# Power.net
KiCad netlist of a schematic drawn in Altium Designer
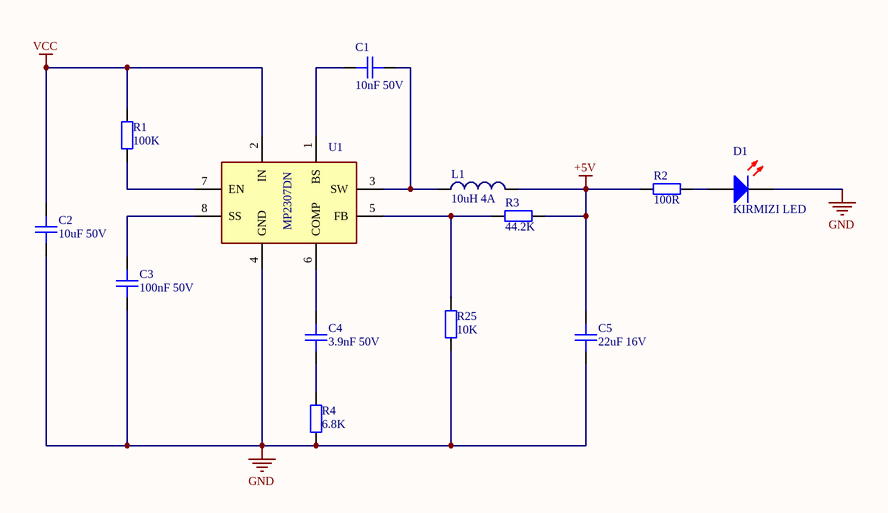
[diagram p0: Power.SchDoc]

(export (version "E")
  (design (tool "Eeschema 10.0.6"))
  (components
    (comp (ref "C1")
      (value "CAP CER 10000PF 50V X7R 0805")
      (footprint "CAP 0805/2012")
      (description "10000pF ±10% 50V Ceramic Capacitor X7R 0805 (2012 Metric)")
      (fields (field (name "DEGER") "10nF 50V"))
      (libsource (lib "PROJE") (part "10nF 50V 0805"))
    )
    (comp (ref "C2")
      (value "CAP CER 10UF 50V X5R 1206")
      (footprint "CAP 1206/3216")
      (description "10µF ±10% 50V Ceramic Capacitor X5R 1206 (3216 Metric)")
      (fields (field (name "DEGER") "10uF 50V"))
      (libsource (lib "PROJE") (part "10uF 50V 1206"))
    )
    (comp (ref "C3")
      (value "CAP CER 0.1UF 50V X7R 0805")
      (footprint "CAP 0805/2012")
      (description "0.1µF ±10% 50V Ceramic Capacitor X7R 0805 (2012 Metric)")
      (fields (field (name "DEGER") "100nF 50V"))
      (libsource (lib "PROJE") (part "100nF 50V 0805"))
    )
    (comp (ref "C4")
      (value "CAP CER 3900PF 50V X7R 0805")
      (footprint "CAP 0805/2012")
      (description "3900pF ±10% 50V Ceramic Capacitor X7R 0805 (2012 Metric)")
      (fields (field (name "DEGER") "3.9nF 50V"))
      (libsource (lib "PROJE") (part "3.9nF 50V 0805"))
    )
    (comp (ref "C5")
      (value "CAP CERAMIC 22UF 16V X7S 20% PAD")
      (footprint "CAP 1206/3216")
      (description "22µF ±20% 16V Ceramic Capacitor X7S 1206 (3216 Metric)")
      (fields (field (name "DEGER") "22uF 16V"))
      (libsource (lib "PROJE") (part "22uF 16V 1206"))
    )
    (comp (ref "D1")
      (value "Red 645nm LED Indication - Discrete 1.8V 0805")
      (footprint "SMD: LED 0805/2012 RED")
      (description "LED RED DIFFUSED 0805 SMD")
      (fields (field (name "DEGER") "KIRMIZI LED"))
      (libsource (lib "PROJE") (part "LED_Kırmızı"))
    )
    (comp (ref "L1")
      (value "FIXED IND 10UH 4A 68 MOHM SMD")
      (footprint "ASPI-0630LR-100M-T15")
      (description "10µH Shielded Molded Inductor 4A 68mOhm Max Nonstandard")
      (fields (field (name "DEGER") "10uH 4A"))
      (libsource (lib "PROJE") (part "10uH 4A"))
    )
    (comp (ref "R1")
      (value "RES SMD 100K OHM 1% 1/8W 0805")
      (footprint "RES_0805")
      (description "100 kOhms ±1% 0.125W, 1/8W Chip Resistor 0805 (2012 Metric) Moisture Resistant Thick Film")
      (fields (field (name "DEGER") "100K"))
      (libsource (lib "PROJE") (part "100K 0805"))
    )
    (comp (ref "R2")
      (value "RES SMD 100 OHM 1% 1/8W 0805")
      (footprint "RES_0805")
      (description "100 Ohms ±1% 0.125W, 1/8W Chip Resistor 0805 (2012 Metric) Moisture Resistant Thick Film")
      (fields (field (name "DEGER") "100R"))
      (libsource (lib "PROJE") (part "100R 0805"))
    )
    (comp (ref "R3")
      (value "RES SMD 44.2K OHM 1% 1/8W 0805")
      (footprint "RES_0805")
      (description "44.2 kOhms ±1% 0.125W, 1/8W Chip Resistor 0805 (2012 Metric) Moisture Resistant Thick Film")
      (fields (field (name "DEGER") "44.2K"))
      (libsource (lib "PROJE") (part "44.2K 0805"))
    )
    (comp (ref "R4")
      (value "RES SMD 6.8K OHM 1% 1/8W 0805")
      (footprint "RES_0805")
      (description "6.8 kOhms ±1% 0.125W, 1/8W Chip Resistor 0805 (2012 Metric) Moisture Resistant Thick Film")
      (fields (field (name "DEGER") "6.8K"))
      (libsource (lib "PROJE") (part "6.8K 0805"))
    )
    (comp (ref "R25")
      (value "RES SMD 10K OHM 1% 1/8W 0805")
      (footprint "RES_0805")
      (description "10 kOhms ±1% 0.125W, 1/8W Chip Resistor 0805 (2012 Metric) Moisture Resistant Thick Film")
      (fields (field (name "DEGER") "10K"))
      (libsource (lib "PROJE") (part "10K 0805"))
    )
    (comp (ref "U1")
      (value "IC REG BUCK ADJUSTABLE 3A 8SOIC")
      (footprint "SOIC8_PAD")
      (fields (field (name "DEGER") "MP2307DN"))
      (libsource (lib "PROJE") (part "MP2307DN"))
    )
  )
  (nets
    (net (code "1") (name "+5V") (class "Default")
      (node (ref "C5") (pin "2") (pinfunction "2_2") (pintype "passive"))
      (node (ref "L1") (pin "2") (pinfunction "2_2") (pintype "passive"))
      (node (ref "R2") (pin "1") (pinfunction "1_1") (pintype "passive"))
      (node (ref "R3") (pin "2") (pinfunction "2_2") (pintype "passive"))
    )
    (net (code "2") (name "GND") (class "Default")
      (node (ref "C2") (pin "1") (pinfunction "1_1") (pintype "passive"))
      (node (ref "C3") (pin "1") (pinfunction "1_1") (pintype "passive"))
      (node (ref "C5") (pin "1") (pinfunction "1_1") (pintype "passive"))
      (node (ref "D1") (pin "2") (pinfunction "K_2") (pintype "passive"))
      (node (ref "R25") (pin "1") (pinfunction "1_1") (pintype "passive"))
      (node (ref "R4") (pin "1") (pinfunction "1_1") (pintype "passive"))
      (node (ref "U1") (pin "4") (pinfunction "GND_4") (pintype "passive"))
    )
    (net (code "3") (name "Net-(C4-Pad1)") (class "Default")
      (node (ref "C4") (pin "1") (pinfunction "1_1") (pintype "passive"))
      (node (ref "R4") (pin "2") (pinfunction "2_2") (pintype "passive"))
    )
    (net (code "4") (name "Net-(D1-A)") (class "Default")
      (node (ref "D1") (pin "1") (pinfunction "A_1") (pintype "passive"))
      (node (ref "R2") (pin "2") (pinfunction "2_2") (pintype "passive"))
    )
    (net (code "5") (name "Net-(U1-BS)") (class "Default")
      (node (ref "C1") (pin "1") (pinfunction "1_1") (pintype "passive"))
      (node (ref "U1") (pin "1") (pinfunction "BS_1") (pintype "passive"))
    )
    (net (code "6") (name "Net-(U1-COMP)") (class "Default")
      (node (ref "C4") (pin "2") (pinfunction "2_2") (pintype "passive"))
      (node (ref "U1") (pin "6") (pinfunction "COMP_6") (pintype "passive"))
    )
    (net (code "7") (name "Net-(U1-EN)") (class "Default")
      (node (ref "R1") (pin "1") (pinfunction "1_1") (pintype "passive"))
      (node (ref "U1") (pin "7") (pinfunction "EN_7") (pintype "passive"))
    )
    (net (code "8") (name "Net-(U1-FB)") (class "Default")
      (node (ref "R25") (pin "2") (pinfunction "2_2") (pintype "passive"))
      (node (ref "R3") (pin "1") (pinfunction "1_1") (pintype "passive"))
      (node (ref "U1") (pin "5") (pinfunction "FB_5") (pintype "passive"))
    )
    (net (code "9") (name "Net-(U1-SS)") (class "Default")
      (node (ref "C3") (pin "2") (pinfunction "2_2") (pintype "passive"))
      (node (ref "U1") (pin "8") (pinfunction "SS_8") (pintype "passive"))
    )
    (net (code "10") (name "Net-(U1-SW)") (class "Default")
      (node (ref "C1") (pin "2") (pinfunction "2_2") (pintype "passive"))
      (node (ref "L1") (pin "1") (pinfunction "1_1") (pintype "passive"))
      (node (ref "U1") (pin "3") (pinfunction "SW_3") (pintype "passive"))
    )
    (net (code "11") (name "VCC") (class "Default")
      (node (ref "C2") (pin "2") (pinfunction "2_2") (pintype "passive"))
      (node (ref "R1") (pin "2") (pinfunction "2_2") (pintype "passive"))
      (node (ref "U1") (pin "2") (pinfunction "IN_2") (pintype "passive"))
    )
  )
)
